# UART_DEBUG.net
KiCad netlist of a schematic drawn in Altium Designer
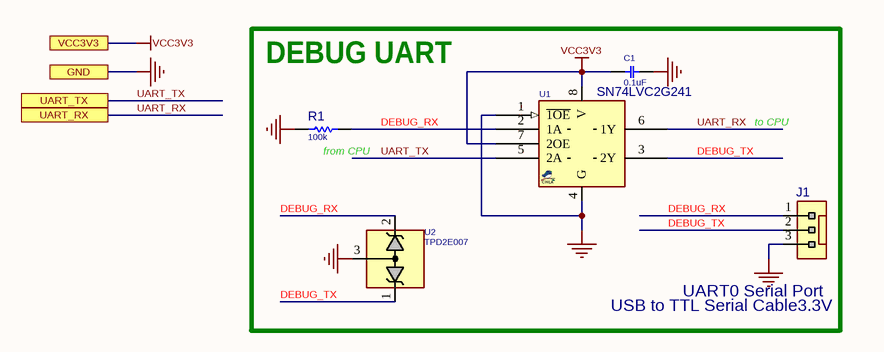
[diagram p0: UART_DEBUG.SchDoc]

(export (version "E")
  (design (tool "Eeschema 10.0.6"))
  (components
    (comp (ref "C1")
      (value "0.1uF")
      (footprint "C0402")
      (description "CAP, MLCC")
      (fields (field (name "MANF_P#") "GRM155R71H104KE14D") (field (name "MANF") "Murata"))
      (libsource (lib "mlcc_smd_passive") (part "CAP_SMD_MLCC_100n50TDK"))
    )
    (comp (ref "J1")
      (value "HDRWF_3")
      (footprint "WF_3")
      (description "Header, WF, Pitch: 2.54mm")
      (libsource (lib "conn_wire2board") (part "HDRWF_3"))
    )
    (comp (ref "R1")
      (value "100k")
      (footprint "R0402")
      (description "RESISTOR, SMD, THICK FILM, YAGEO")
      (libsource (lib "passive_res_smd") (part "RES_SMD_100K_0402YK"))
    )
    (comp (ref "U1")
      (value "SN74LVC2G241")
      (footprint "SOG50_8")
      (description "Buffer/Line Driver, Dual, 3-State Outputs")
      (fields (field (name "MANF") "Texas Instruments") (field (name "MANF_P#") "SN74LVC2G241DCU"))
      (libsource (lib "buffer_digital") (part "SN74LVC2G241"))
    )
    (comp (ref "U2")
      (value "TPD2E007")
      (footprint "SOT663_3")
      (description "TVS, ESD PROTECT, 2CH, 14VBR, 0.2W")
      (fields (field (name "MANF_P#") "TPD2E007DCKR") (field (name "MANF") "TI"))
      (libsource (lib "protect_tvs_esd_fuse") (part "TVS_X2_TPD2E007"))
    )
  )
  (nets
    (net (code "1") (name "/DEBUG_RX") (class "Default")
      (node (ref "J1") (pin "1") (pinfunction "1_1") (pintype "passive"))
      (node (ref "R1") (pin "2") (pinfunction "2_2") (pintype "passive"))
      (node (ref "U1") (pin "2") (pinfunction "1A_2") (pintype "passive"))
      (node (ref "U2") (pin "2") (pinfunction "IO2_2") (pintype "passive"))
    )
    (net (code "2") (name "/DEBUG_TX") (class "Default")
      (node (ref "J1") (pin "2") (pinfunction "2_2") (pintype "passive"))
      (node (ref "U1") (pin "3") (pinfunction "2Y_3") (pintype "passive"))
      (node (ref "U2") (pin "1") (pinfunction "IO1_1") (pintype "passive"))
    )
    (net (code "3") (name "/UART_RX") (class "Default")
      (node (ref "U1") (pin "6") (pinfunction "1Y_6") (pintype "passive"))
    )
    (net (code "4") (name "/UART_TX") (class "Default")
      (node (ref "U1") (pin "5") (pinfunction "2A_5") (pintype "passive"))
    )
    (net (code "5") (name "GND") (class "Default")
      (node (ref "C1") (pin "2") (pinfunction "2_2") (pintype "passive"))
      (node (ref "J1") (pin "3") (pinfunction "3_3") (pintype "passive"))
      (node (ref "R1") (pin "1") (pinfunction "1_1") (pintype "passive"))
      (node (ref "U1") (pin "1") (pinfunction "~{1OE}_1") (pintype "input"))
      (node (ref "U1") (pin "4") (pinfunction "G_4") (pintype "power_in"))
      (node (ref "U2") (pin "3") (pinfunction "GND_3") (pintype "passive"))
    )
    (net (code "6") (name "VCC3V3") (class "Default")
      (node (ref "C1") (pin "1") (pinfunction "1_1") (pintype "passive"))
      (node (ref "U1") (pin "7") (pinfunction "2OE_7") (pintype "passive"))
      (node (ref "U1") (pin "8") (pinfunction "V_8") (pintype "power_in"))
    )
  )
)
